# Sensors-V1.net
KiCad netlist of a schematic drawn in EAGLE
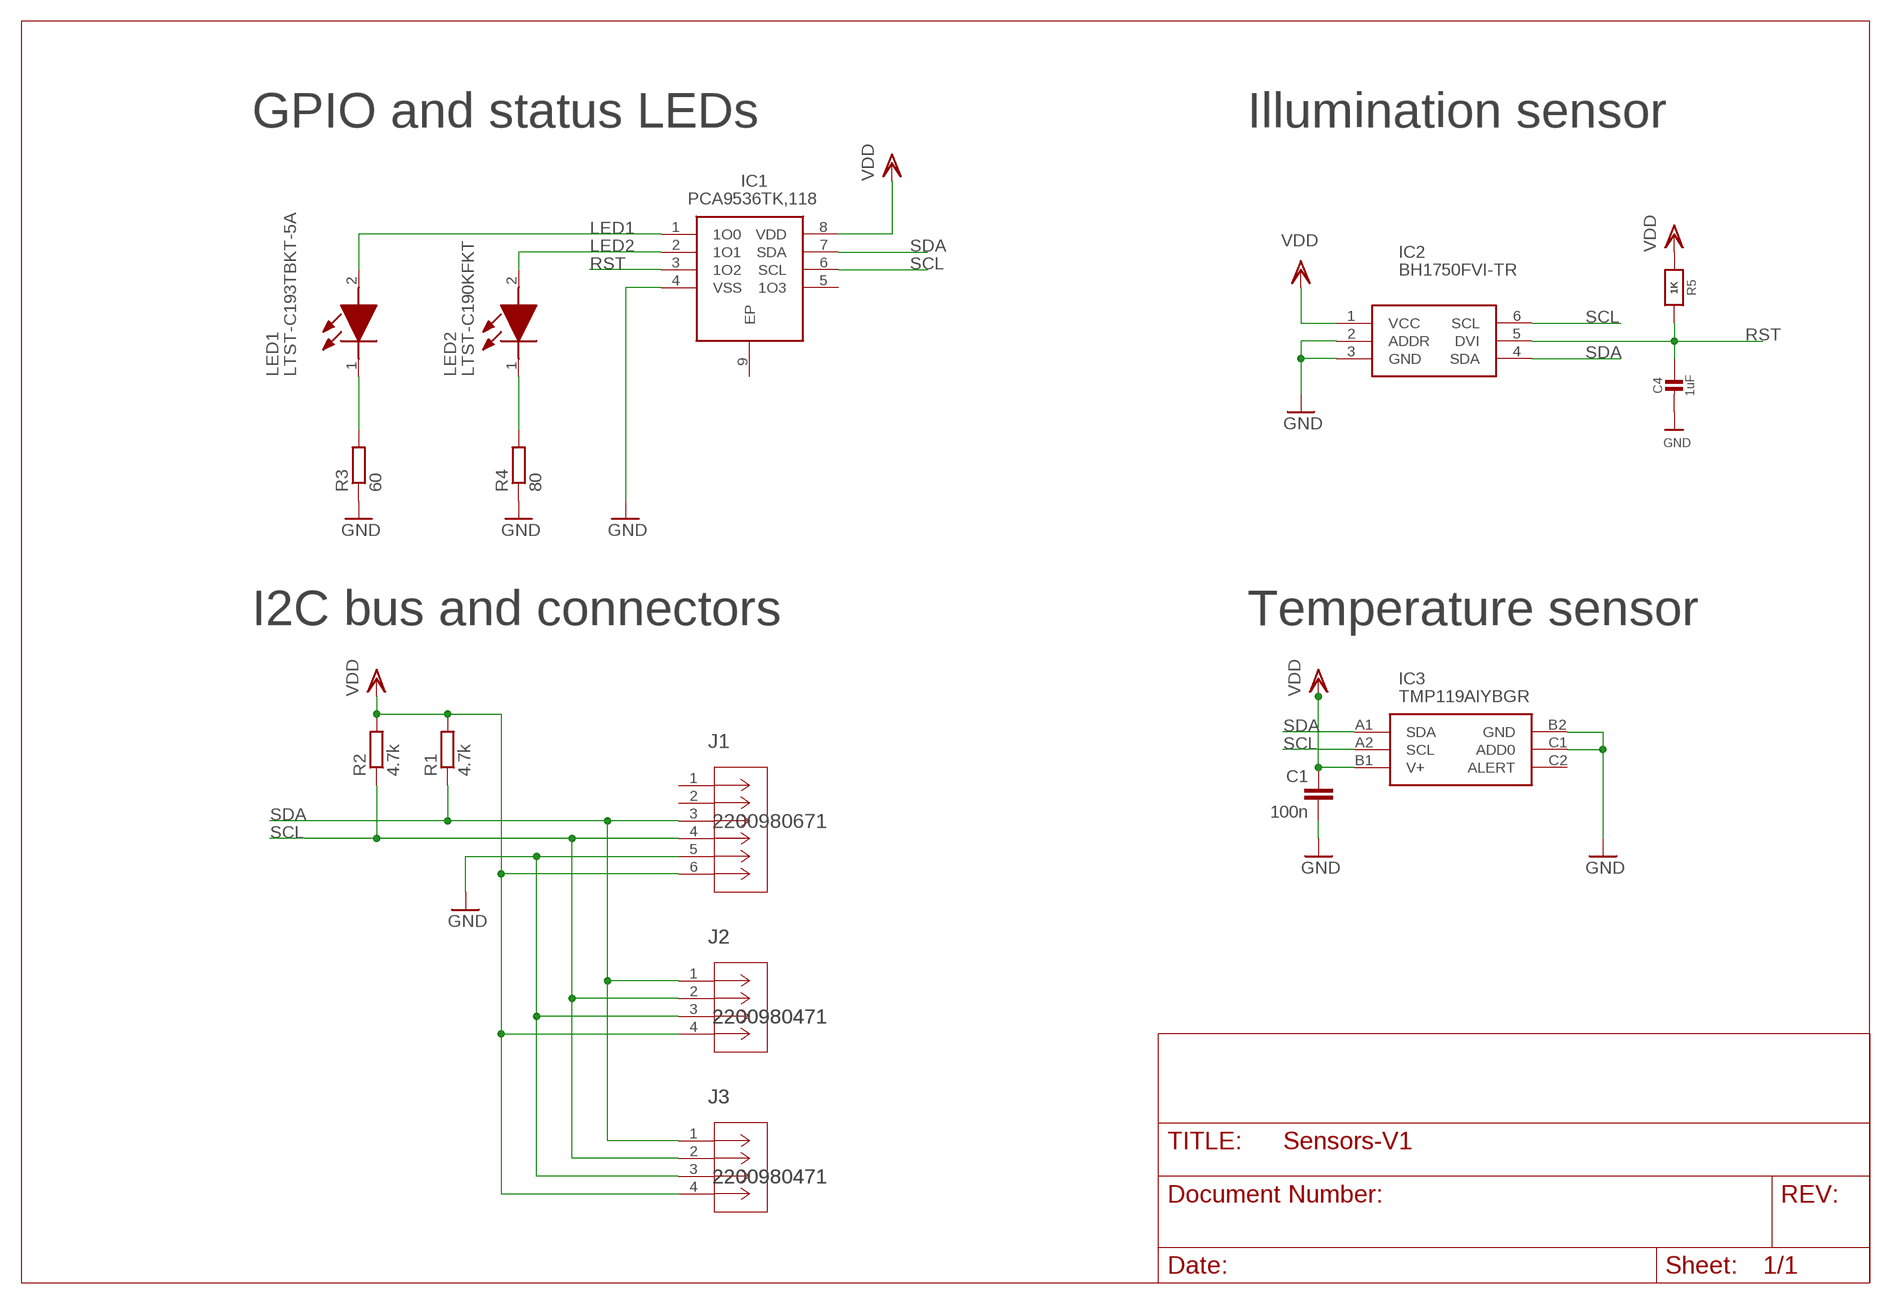
[diagram p0: schematic, sheet 1]

(export (version "E")
  (design (tool "Eeschema 10.0.6"))
  (components
    (comp (ref "C1")
      (value "100n")
      (footprint "eagle-import:C0603")
      (libsource (lib "eagle-import") (part "C-EUC0603"))
    )
    (comp (ref "C4")
      (value "1uF")
      (footprint "eagle-import:0603-NO")
      (libsource (lib "eagle-import") (part "CAP_CERAMIC0603_NO"))
    )
    (comp (ref "IC1")
      (value "PCA9536TK,118")
      (footprint "eagle-import:SON50P300X300X100-9N")
      (libsource (lib "eagle-import") (part "PCA9536TK,118"))
    )
    (comp (ref "IC2")
      (value "BH1750FVI-TR")
      (footprint "eagle-import:WSOF6")
      (libsource (lib "eagle-import") (part "BH1750FVI-TR"))
    )
    (comp (ref "IC3")
      (value "TMP119AIYBGR")
      (footprint "eagle-import:BGA6C40P2X3_95X149X52")
      (fields (field (name "MOUSER_PART_NUMBER") "595-TMP119AIYBGR"))
      (libsource (lib "eagle-import") (part "TMP119AIYBGR"))
    )
    (comp (ref "J1")
      (value "2200980671")
      (footprint "eagle-import:CONN_2200980000-SD_06_MOL")
      (fields (field (name "COPYRIGHT") "Copyright (C) 2025 Ultra Librarian. All rights reserved."))
      (libsource (lib "eagle-import") (part "2200980671"))
    )
    (comp (ref "J2")
      (value "2200980471")
      (footprint "eagle-import:CONN_2200980000-SD_04_MOL")
      (fields
        (field (name "MANUFACTURER_PART_NUMBER") "2200970471")
        (field (name "COPYRIGHT") "Copyright (C) 2025 Ultra Librarian. All rights reserved.")
      )
      (libsource (lib "eagle-import") (part "2200980471"))
    )
    (comp (ref "J3")
      (value "2200980471")
      (footprint "eagle-import:CONN_2200980000-SD_04_MOL")
      (fields
        (field (name "MANUFACTURER_PART_NUMBER") "2200970471")
        (field (name "COPYRIGHT") "Copyright (C) 2025 Ultra Librarian. All rights reserved.")
      )
      (libsource (lib "eagle-import") (part "2200980471"))
    )
    (comp (ref "LED1")
      (value "LTST-C193TBKT-5A")
      (footprint "eagle-import:LEDC1608X45N")
      (fields (field (name "MOUSER_PART_NUMBER") "859-LTSTC193TBKT5A"))
      (libsource (lib "eagle-import") (part "LTST-C193TBKT-5A"))
    )
    (comp (ref "LED2")
      (value "LTST-C190KFKT")
      (footprint "eagle-import:LEDC1607X80N")
      (fields (field (name "MOUSER_PART_NUMBER") "859-LTST-C190KFKT"))
      (libsource (lib "eagle-import") (part "LTST-C190KFKT"))
    )
    (comp (ref "R1")
      (value "4.7k")
      (footprint "eagle-import:R0603")
      (libsource (lib "eagle-import") (part "R_JLMR0603"))
    )
    (comp (ref "R2")
      (value "4.7k")
      (footprint "eagle-import:R0603")
      (libsource (lib "eagle-import") (part "R_JLMR0603"))
    )
    (comp (ref "R3")
      (value "60")
      (footprint "eagle-import:R0603")
      (libsource (lib "eagle-import") (part "R_JLMR0603"))
    )
    (comp (ref "R4")
      (value "80")
      (footprint "eagle-import:R0603")
      (libsource (lib "eagle-import") (part "R_JLMR0603"))
    )
    (comp (ref "R5")
      (value "1K")
      (footprint "eagle-import:0603-NO")
      (libsource (lib "eagle-import") (part "RESISTOR_0603_NOOUT"))
    )
  )
  (nets
    (net (code "1") (name "/LED1") (class "Default")
      (node (ref "IC1") (pin "1") (pinfunction "1O0_1") (pintype "bidirectional"))
      (node (ref "LED1") (pin "2") (pinfunction "A_2") (pintype "bidirectional"))
    )
    (net (code "2") (name "/LED2") (class "Default")
      (node (ref "IC1") (pin "2") (pinfunction "1O1_2") (pintype "bidirectional"))
      (node (ref "LED2") (pin "2") (pinfunction "A_2") (pintype "bidirectional"))
    )
    (net (code "3") (name "/RST") (class "Default")
      (node (ref "C4") (pin "1") (pinfunction "1_1") (pintype "passive"))
      (node (ref "IC1") (pin "3") (pinfunction "1O2_3") (pintype "bidirectional"))
      (node (ref "IC2") (pin "5") (pinfunction "DVI_5") (pintype "bidirectional"))
      (node (ref "R5") (pin "2") (pinfunction "2_2") (pintype "passive"))
    )
    (net (code "4") (name "/SCL") (class "Default")
      (node (ref "IC1") (pin "6") (pinfunction "SCL_6") (pintype "bidirectional"))
      (node (ref "IC2") (pin "6") (pinfunction "SCL_6") (pintype "bidirectional"))
      (node (ref "IC3") (pin "A2") (pinfunction "SCL_A2") (pintype "bidirectional"))
      (node (ref "J1") (pin "4") (pinfunction "4_4") (pintype "passive"))
      (node (ref "J2") (pin "2") (pinfunction "2_2") (pintype "passive"))
      (node (ref "J3") (pin "2") (pinfunction "2_2") (pintype "passive"))
      (node (ref "R2") (pin "1") (pinfunction "1_1") (pintype "passive"))
    )
    (net (code "5") (name "/SDA") (class "Default")
      (node (ref "IC1") (pin "7") (pinfunction "SDA_7") (pintype "bidirectional"))
      (node (ref "IC2") (pin "4") (pinfunction "SDA_4") (pintype "bidirectional"))
      (node (ref "IC3") (pin "A1") (pinfunction "SDA_A1") (pintype "bidirectional"))
      (node (ref "J1") (pin "3") (pinfunction "3_3") (pintype "passive"))
      (node (ref "J2") (pin "1") (pinfunction "1_1") (pintype "passive"))
      (node (ref "J3") (pin "1") (pinfunction "1_1") (pintype "passive"))
      (node (ref "R1") (pin "1") (pinfunction "1_1") (pintype "passive"))
    )
    (net (code "6") (name "GND") (class "Default")
      (node (ref "C1") (pin "2") (pinfunction "2_2") (pintype "passive"))
      (node (ref "C4") (pin "2") (pinfunction "2_2") (pintype "passive"))
      (node (ref "IC1") (pin "4") (pinfunction "VSS_4") (pintype "bidirectional"))
      (node (ref "IC2") (pin "2") (pinfunction "ADDR_2") (pintype "bidirectional"))
      (node (ref "IC2") (pin "3") (pinfunction "GND_3") (pintype "bidirectional"))
      (node (ref "IC3") (pin "B2") (pinfunction "GND_B2") (pintype "bidirectional"))
      (node (ref "IC3") (pin "C1") (pinfunction "ADD0_C1") (pintype "bidirectional"))
      (node (ref "J1") (pin "5") (pinfunction "5_5") (pintype "passive"))
      (node (ref "J2") (pin "3") (pinfunction "3_3") (pintype "passive"))
      (node (ref "J3") (pin "3") (pinfunction "3_3") (pintype "passive"))
      (node (ref "R3") (pin "1") (pinfunction "1_1") (pintype "passive"))
      (node (ref "R4") (pin "1") (pinfunction "1_1") (pintype "passive"))
    )
    (net (code "7") (name "Net-(LED1-K)") (class "Default")
      (node (ref "LED1") (pin "1") (pinfunction "K_1") (pintype "bidirectional"))
      (node (ref "R3") (pin "2") (pinfunction "2_2") (pintype "passive"))
    )
    (net (code "8") (name "Net-(LED2-K)") (class "Default")
      (node (ref "LED2") (pin "1") (pinfunction "K_1") (pintype "bidirectional"))
      (node (ref "R4") (pin "2") (pinfunction "2_2") (pintype "passive"))
    )
    (net (code "9") (name "VDD") (class "Default")
      (node (ref "C1") (pin "1") (pinfunction "1_1") (pintype "passive"))
      (node (ref "IC1") (pin "8") (pinfunction "VDD_8") (pintype "bidirectional"))
      (node (ref "IC2") (pin "1") (pinfunction "VCC_1") (pintype "bidirectional"))
      (node (ref "IC3") (pin "B1") (pinfunction "V+_B1") (pintype "bidirectional"))
      (node (ref "J1") (pin "6") (pinfunction "6_6") (pintype "passive"))
      (node (ref "J2") (pin "4") (pinfunction "4_4") (pintype "passive"))
      (node (ref "J3") (pin "4") (pinfunction "4_4") (pintype "passive"))
      (node (ref "R1") (pin "2") (pinfunction "2_2") (pintype "passive"))
      (node (ref "R2") (pin "2") (pinfunction "2_2") (pintype "passive"))
      (node (ref "R5") (pin "1") (pinfunction "1_1") (pintype "passive"))
    )
    (net (code "10") (name "unconnected-(IC1-1O3-Pad5)") (class "Default")
      (node (ref "IC1") (pin "5") (pinfunction "1O3_5") (pintype "bidirectional"))
    )
    (net (code "11") (name "unconnected-(IC1-EP-Pad9)") (class "Default")
      (node (ref "IC1") (pin "9") (pinfunction "EP_9") (pintype "bidirectional"))
    )
    (net (code "12") (name "unconnected-(IC3-ALERT-PadC2)") (class "Default")
      (node (ref "IC3") (pin "C2") (pinfunction "ALERT_C2") (pintype "bidirectional"))
    )
    (net (code "13") (name "unconnected-(J1-Pad1)") (class "Default")
      (node (ref "J1") (pin "1") (pinfunction "1_1") (pintype "passive"))
    )
    (net (code "14") (name "unconnected-(J1-Pad2)") (class "Default")
      (node (ref "J1") (pin "2") (pinfunction "2_2") (pintype "passive"))
    )
  )
)
